# spuung-ap-v_0_0_1a.net
KiCad netlist of a schematic drawn in EAGLE
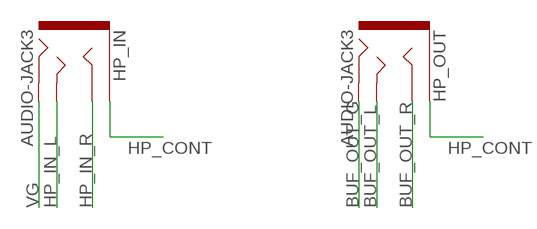
[diagram p0: schematic, sheet 1]
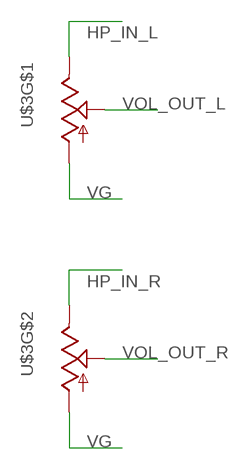
[diagram p1: schematic, sheet 2]
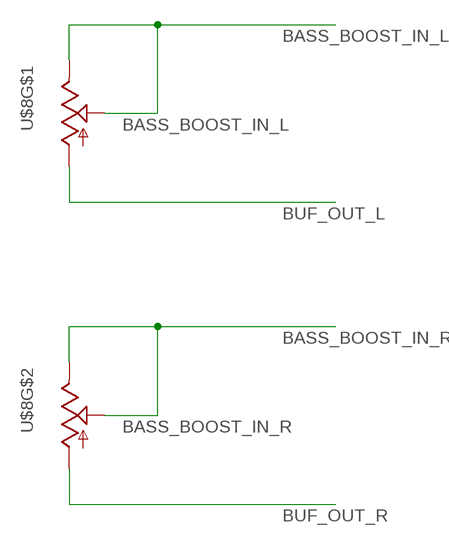
[diagram p2: schematic, sheet 3]
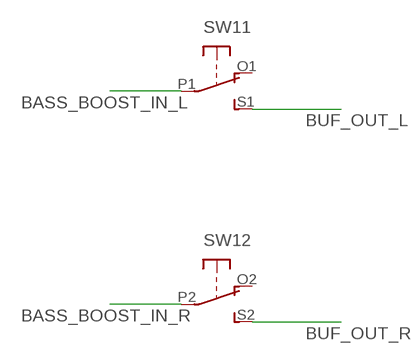
[diagram p3: schematic, sheet 4]
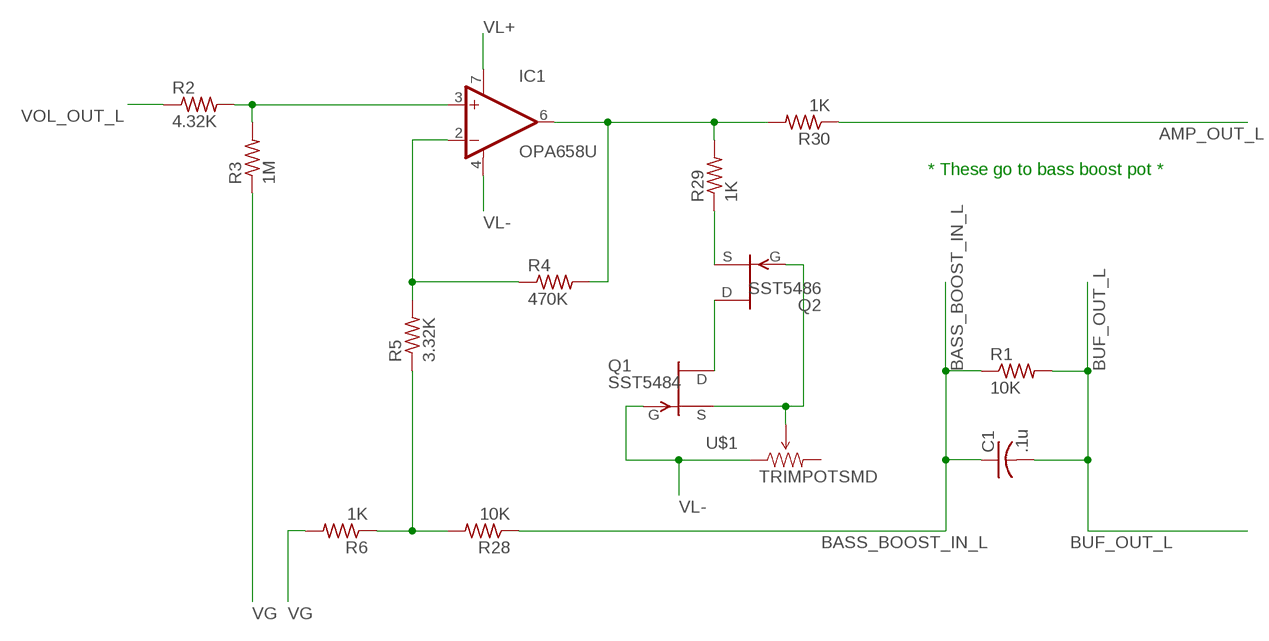
[diagram p4: schematic, sheet 5]
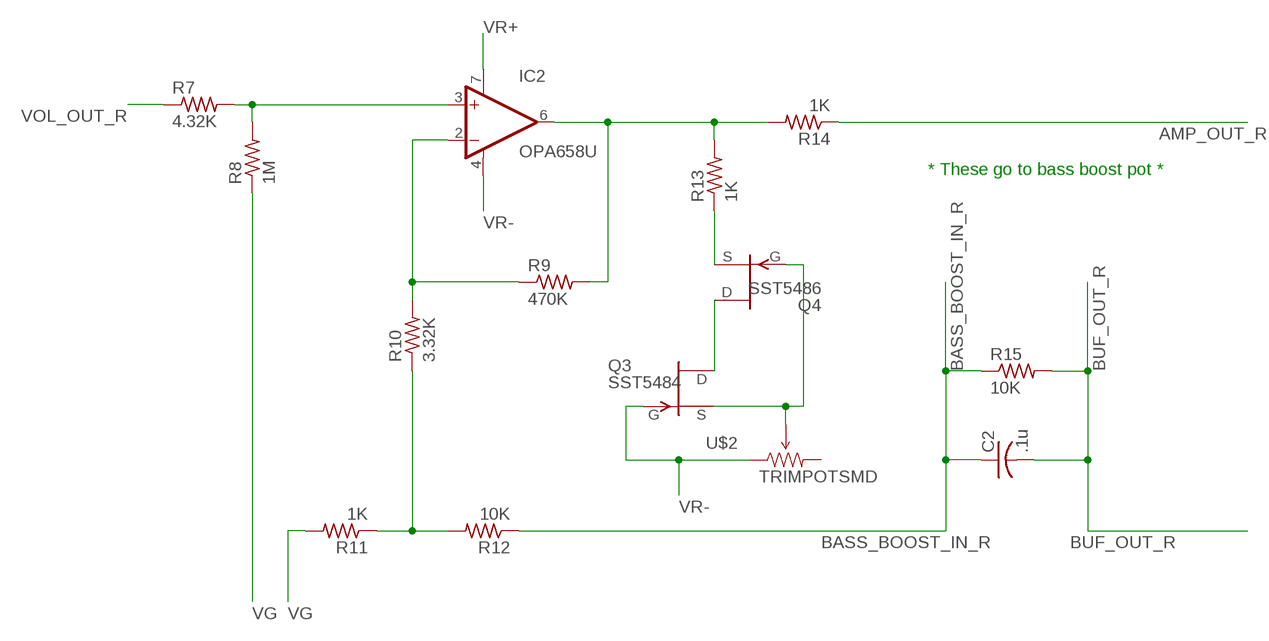
[diagram p5: schematic, sheet 6]
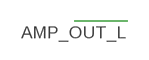
[diagram p6: schematic, sheet 7]
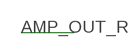
[diagram p7: schematic, sheet 8]

(export (version "E")
  (design (tool "Eeschema 10.0.6"))
  (components
    (comp (ref "HP_IN")
      (value "AUDIO-JACK3")
      (footprint "eagle-import:AUDIO-JACK-TRRS-SMD")
      (libsource (lib "eagle-import") (part "AUDIO-JACK3"))
    )
    (comp (ref "HP_OUT")
      (value "AUDIO-JACK3")
      (footprint "eagle-import:AUDIO-JACK-TRRS-SMD")
      (libsource (lib "eagle-import") (part "AUDIO-JACK3"))
    )
    (comp (ref "C1")
      (value ".1u")
      (footprint "eagle-import:C0805")
      (libsource (lib "eagle-import") (part "C-USC0805"))
    )
    (comp (ref "IC1")
      (value "OPA658U")
      (footprint "eagle-import:SO08")
      (fields (field (name "MPN") "AD8001ARZ"))
      (libsource (lib "eagle-import") (part "OPA658U"))
    )
    (comp (ref "Q1")
      (value "SST5484")
      (footprint "eagle-import:SOT23")
      (libsource (lib "eagle-import") (part "?548SST4"))
    )
    (comp (ref "Q2")
      (value "SST5486")
      (footprint "eagle-import:SOT23")
      (libsource (lib "eagle-import") (part "?548SST6"))
    )
    (comp (ref "R1")
      (value "10K")
      (footprint "eagle-import:R0805")
      (libsource (lib "eagle-import") (part "R-US_R0805"))
    )
    (comp (ref "R2")
      (value "4.32K")
      (footprint "eagle-import:R0805")
      (libsource (lib "eagle-import") (part "R-US_R0805"))
    )
    (comp (ref "R3")
      (value "1M")
      (footprint "eagle-import:R0805")
      (libsource (lib "eagle-import") (part "R-US_R0805"))
    )
    (comp (ref "R4")
      (value "470K")
      (footprint "eagle-import:R0805")
      (libsource (lib "eagle-import") (part "R-US_R0805"))
    )
    (comp (ref "R5")
      (value "3.32K")
      (footprint "eagle-import:R0805")
      (libsource (lib "eagle-import") (part "R-US_R0805"))
    )
    (comp (ref "R6")
      (value "1K")
      (footprint "eagle-import:R0805")
      (libsource (lib "eagle-import") (part "R-US_R0805"))
    )
    (comp (ref "R28")
      (value "10K")
      (footprint "eagle-import:R0805")
      (libsource (lib "eagle-import") (part "R-US_R0805"))
    )
    (comp (ref "R29")
      (value "1K")
      (footprint "eagle-import:R0805")
      (libsource (lib "eagle-import") (part "R-US_R0805"))
    )
    (comp (ref "R30")
      (value "1K")
      (footprint "eagle-import:R0805")
      (libsource (lib "eagle-import") (part "R-US_R0805"))
    )
    (comp (ref "U$1")
      (value "TRIMPOTSMD")
      (footprint "eagle-import:TRIMPOT-3MM")
      (libsource (lib "eagle-import") (part "TRIMPOTSMD"))
    )
    (comp (ref "U$8")
      (value "ALPS_BLUE")
      (footprint "eagle-import:ALPS_RK27")
      (libsource (lib "eagle-import") (part "ALPS_BLUE"))
    )
    (comp (ref "C2")
      (value ".1u")
      (footprint "eagle-import:C0805")
      (libsource (lib "eagle-import") (part "C-USC0805"))
    )
    (comp (ref "IC2")
      (value "OPA658U")
      (footprint "eagle-import:SO08")
      (fields (field (name "MPN") "AD8001ARZ"))
      (libsource (lib "eagle-import") (part "OPA658U"))
    )
    (comp (ref "Q3")
      (value "SST5484")
      (footprint "eagle-import:SOT23")
      (libsource (lib "eagle-import") (part "?548SST4"))
    )
    (comp (ref "Q4")
      (value "SST5486")
      (footprint "eagle-import:SOT23")
      (libsource (lib "eagle-import") (part "?548SST6"))
    )
    (comp (ref "R7")
      (value "4.32K")
      (footprint "eagle-import:R0805")
      (libsource (lib "eagle-import") (part "R-US_R0805"))
    )
    (comp (ref "R8")
      (value "1M")
      (footprint "eagle-import:R0805")
      (libsource (lib "eagle-import") (part "R-US_R0805"))
    )
    (comp (ref "R9")
      (value "470K")
      (footprint "eagle-import:R0805")
      (libsource (lib "eagle-import") (part "R-US_R0805"))
    )
    (comp (ref "R10")
      (value "3.32K")
      (footprint "eagle-import:R0805")
      (libsource (lib "eagle-import") (part "R-US_R0805"))
    )
    (comp (ref "R11")
      (value "1K")
      (footprint "eagle-import:R0805")
      (libsource (lib "eagle-import") (part "R-US_R0805"))
    )
    (comp (ref "R12")
      (value "10K")
      (footprint "eagle-import:R0805")
      (libsource (lib "eagle-import") (part "R-US_R0805"))
    )
    (comp (ref "R13")
      (value "1K")
      (footprint "eagle-import:R0805")
      (libsource (lib "eagle-import") (part "R-US_R0805"))
    )
    (comp (ref "R14")
      (value "1K")
      (footprint "eagle-import:R0805")
      (libsource (lib "eagle-import") (part "R-US_R0805"))
    )
    (comp (ref "R15")
      (value "10K")
      (footprint "eagle-import:R0805")
      (libsource (lib "eagle-import") (part "R-US_R0805"))
    )
    (comp (ref "U$2")
      (value "TRIMPOTSMD")
      (footprint "eagle-import:TRIMPOT-3MM")
      (libsource (lib "eagle-import") (part "TRIMPOTSMD"))
    )
    (comp (ref "U$3")
      (value "ALPS_BLUE")
      (footprint "eagle-import:ALPS_RK27")
      (libsource (lib "eagle-import") (part "ALPS_BLUE"))
    )
    (comp (ref "SW1")
      (value "DPDT-EG1390")
      (footprint "eagle-import:EG1390")
      (libsource (lib "eagle-import") (part "DPDT-EG1390"))
    )
  )
  (nets
    (net (code "1") (name "AMP_OUT_L") (class "Default")
      (node (ref "R30") (pin "1") (pinfunction "1_1") (pintype "passive"))
    )
    (net (code "2") (name "AMP_OUT_R") (class "Default")
      (node (ref "R14") (pin "1") (pinfunction "1_1") (pintype "passive"))
    )
    (net (code "3") (name "BASS_BOOST_IN_L") (class "Default")
      (node (ref "C1") (pin "1") (pinfunction "1_1") (pintype "passive"))
      (node (ref "R1") (pin "1") (pinfunction "1_1") (pintype "passive"))
      (node (ref "R28") (pin "1") (pinfunction "1_1") (pintype "passive"))
      (node (ref "SW1") (pin "P1") (pinfunction "P_P1") (pintype "passive"))
      (node (ref "U$8") (pin "I1") (pinfunction "3_I1") (pintype "passive"))
      (node (ref "U$8") (pin "O1") (pinfunction "2_O1") (pintype "passive"))
    )
    (net (code "4") (name "BASS_BOOST_IN_R") (class "Default")
      (node (ref "C2") (pin "1") (pinfunction "1_1") (pintype "passive"))
      (node (ref "R12") (pin "1") (pinfunction "1_1") (pintype "passive"))
      (node (ref "R15") (pin "1") (pinfunction "1_1") (pintype "passive"))
      (node (ref "SW1") (pin "P2") (pinfunction "P_P2") (pintype "passive"))
      (node (ref "U$8") (pin "I2") (pinfunction "3_I2") (pintype "passive"))
      (node (ref "U$8") (pin "O2") (pinfunction "2_O2") (pintype "passive"))
    )
    (net (code "5") (name "BUF_OUT_G") (class "Default")
      (node (ref "HP_OUT") (pin "RING2") (pinfunction "RING2_RING2") (pintype "bidirectional"))
    )
    (net (code "6") (name "BUF_OUT_L") (class "Default")
      (node (ref "C1") (pin "2") (pinfunction "2_2") (pintype "passive"))
      (node (ref "HP_OUT") (pin "TIP") (pinfunction "TIP_TIP") (pintype "bidirectional"))
      (node (ref "R1") (pin "2") (pinfunction "2_2") (pintype "passive"))
      (node (ref "SW1") (pin "S1") (pinfunction "S_S1") (pintype "passive"))
      (node (ref "U$8") (pin "G1") (pinfunction "1_G1") (pintype "passive"))
    )
    (net (code "7") (name "BUF_OUT_R") (class "Default")
      (node (ref "C2") (pin "2") (pinfunction "2_2") (pintype "passive"))
      (node (ref "HP_OUT") (pin "RING1") (pinfunction "RING1_RING1") (pintype "bidirectional"))
      (node (ref "R15") (pin "2") (pinfunction "2_2") (pintype "passive"))
      (node (ref "SW1") (pin "S2") (pinfunction "S_S2") (pintype "passive"))
      (node (ref "U$8") (pin "G2") (pinfunction "1_G2") (pintype "passive"))
    )
    (net (code "8") (name "HP_CONT") (class "Default")
      (node (ref "HP_IN") (pin "EARTH") (pinfunction "EARTH_EARTH") (pintype "bidirectional"))
      (node (ref "HP_OUT") (pin "EARTH") (pinfunction "EARTH_EARTH") (pintype "bidirectional"))
    )
    (net (code "9") (name "HP_IN_L") (class "Default")
      (node (ref "HP_IN") (pin "TIP") (pinfunction "TIP_TIP") (pintype "bidirectional"))
      (node (ref "U$3") (pin "I1") (pinfunction "3_I1") (pintype "passive"))
    )
    (net (code "10") (name "HP_IN_R") (class "Default")
      (node (ref "HP_IN") (pin "RING1") (pinfunction "RING1_RING1") (pintype "bidirectional"))
      (node (ref "U$3") (pin "I2") (pinfunction "3_I2") (pintype "passive"))
    )
    (net (code "11") (name "Net-(IC1-+IN)") (class "Default")
      (node (ref "IC1") (pin "3") (pinfunction "+IN_3") (pintype "input"))
      (node (ref "R2") (pin "2") (pinfunction "2_2") (pintype "passive"))
      (node (ref "R3") (pin "2") (pinfunction "2_2") (pintype "passive"))
    )
    (net (code "12") (name "Net-(IC1--IN)") (class "Default")
      (node (ref "IC1") (pin "2") (pinfunction "-IN_2") (pintype "input"))
      (node (ref "R4") (pin "1") (pinfunction "1_1") (pintype "passive"))
      (node (ref "R5") (pin "2") (pinfunction "2_2") (pintype "passive"))
    )
    (net (code "13") (name "Net-(IC1-OUT)") (class "Default")
      (node (ref "IC1") (pin "6") (pinfunction "OUT_6") (pintype "output"))
      (node (ref "R29") (pin "2") (pinfunction "2_2") (pintype "passive"))
      (node (ref "R30") (pin "2") (pinfunction "2_2") (pintype "passive"))
      (node (ref "R4") (pin "2") (pinfunction "2_2") (pintype "passive"))
    )
    (net (code "14") (name "Net-(IC2-+IN)") (class "Default")
      (node (ref "IC2") (pin "3") (pinfunction "+IN_3") (pintype "input"))
      (node (ref "R7") (pin "2") (pinfunction "2_2") (pintype "passive"))
      (node (ref "R8") (pin "2") (pinfunction "2_2") (pintype "passive"))
    )
    (net (code "15") (name "Net-(IC2--IN)") (class "Default")
      (node (ref "IC2") (pin "2") (pinfunction "-IN_2") (pintype "input"))
      (node (ref "R10") (pin "2") (pinfunction "2_2") (pintype "passive"))
      (node (ref "R9") (pin "1") (pinfunction "1_1") (pintype "passive"))
    )
    (net (code "16") (name "Net-(IC2-OUT)") (class "Default")
      (node (ref "IC2") (pin "6") (pinfunction "OUT_6") (pintype "output"))
      (node (ref "R13") (pin "2") (pinfunction "2_2") (pintype "passive"))
      (node (ref "R14") (pin "2") (pinfunction "2_2") (pintype "passive"))
      (node (ref "R9") (pin "2") (pinfunction "2_2") (pintype "passive"))
    )
    (net (code "17") (name "Net-(Q1-D)") (class "Default")
      (node (ref "Q1") (pin "1") (pinfunction "D_1") (pintype "passive"))
      (node (ref "Q2") (pin "1") (pinfunction "D_1") (pintype "passive"))
    )
    (net (code "18") (name "Net-(Q1-S)") (class "Default")
      (node (ref "Q1") (pin "2") (pinfunction "S_2") (pintype "passive"))
      (node (ref "Q2") (pin "3") (pinfunction "G_3") (pintype "passive"))
      (node (ref "U$1") (pin "2") (pinfunction "WIPER_2") (pintype "passive"))
    )
    (net (code "19") (name "Net-(Q2-S)") (class "Default")
      (node (ref "Q2") (pin "2") (pinfunction "S_2") (pintype "passive"))
      (node (ref "R29") (pin "1") (pinfunction "1_1") (pintype "passive"))
    )
    (net (code "20") (name "Net-(Q3-D)") (class "Default")
      (node (ref "Q3") (pin "1") (pinfunction "D_1") (pintype "passive"))
      (node (ref "Q4") (pin "1") (pinfunction "D_1") (pintype "passive"))
    )
    (net (code "21") (name "Net-(Q3-S)") (class "Default")
      (node (ref "Q3") (pin "2") (pinfunction "S_2") (pintype "passive"))
      (node (ref "Q4") (pin "3") (pinfunction "G_3") (pintype "passive"))
      (node (ref "U$2") (pin "2") (pinfunction "WIPER_2") (pintype "passive"))
    )
    (net (code "22") (name "Net-(Q4-S)") (class "Default")
      (node (ref "Q4") (pin "2") (pinfunction "S_2") (pintype "passive"))
      (node (ref "R13") (pin "1") (pinfunction "1_1") (pintype "passive"))
    )
    (net (code "23") (name "Net-(R10-Pad1)") (class "Default")
      (node (ref "R10") (pin "1") (pinfunction "1_1") (pintype "passive"))
      (node (ref "R11") (pin "1") (pinfunction "1_1") (pintype "passive"))
      (node (ref "R12") (pin "2") (pinfunction "2_2") (pintype "passive"))
    )
    (net (code "24") (name "Net-(R28-Pad2)") (class "Default")
      (node (ref "R28") (pin "2") (pinfunction "2_2") (pintype "passive"))
      (node (ref "R5") (pin "1") (pinfunction "1_1") (pintype "passive"))
      (node (ref "R6") (pin "1") (pinfunction "1_1") (pintype "passive"))
    )
    (net (code "25") (name "VG") (class "Default")
      (node (ref "HP_IN") (pin "RING2") (pinfunction "RING2_RING2") (pintype "bidirectional"))
      (node (ref "R11") (pin "2") (pinfunction "2_2") (pintype "passive"))
      (node (ref "R3") (pin "1") (pinfunction "1_1") (pintype "passive"))
      (node (ref "R6") (pin "2") (pinfunction "2_2") (pintype "passive"))
      (node (ref "R8") (pin "1") (pinfunction "1_1") (pintype "passive"))
      (node (ref "U$3") (pin "G1") (pinfunction "1_G1") (pintype "passive"))
      (node (ref "U$3") (pin "G2") (pinfunction "1_G2") (pintype "passive"))
    )
    (net (code "26") (name "VL+") (class "Default")
      (node (ref "IC1") (pin "7") (pinfunction "V+_7") (pintype "power_in"))
    )
    (net (code "27") (name "VL-") (class "Default")
      (node (ref "IC1") (pin "4") (pinfunction "V-_4") (pintype "power_in"))
      (node (ref "Q1") (pin "3") (pinfunction "G_3") (pintype "passive"))
      (node (ref "U$1") (pin "1") (pinfunction "CCW_1") (pintype "passive"))
    )
    (net (code "28") (name "VOL_OUT_L") (class "Default")
      (node (ref "R2") (pin "1") (pinfunction "1_1") (pintype "passive"))
      (node (ref "U$3") (pin "O1") (pinfunction "2_O1") (pintype "passive"))
    )
    (net (code "29") (name "VOL_OUT_R") (class "Default")
      (node (ref "R7") (pin "1") (pinfunction "1_1") (pintype "passive"))
      (node (ref "U$3") (pin "O2") (pinfunction "2_O2") (pintype "passive"))
    )
    (net (code "30") (name "VR+") (class "Default")
      (node (ref "IC2") (pin "7") (pinfunction "V+_7") (pintype "power_in"))
    )
    (net (code "31") (name "VR-") (class "Default")
      (node (ref "IC2") (pin "4") (pinfunction "V-_4") (pintype "power_in"))
      (node (ref "Q3") (pin "3") (pinfunction "G_3") (pintype "passive"))
      (node (ref "U$2") (pin "1") (pinfunction "CCW_1") (pintype "passive"))
    )
    (net (code "32") (name "unconnected-(SW1A-O-PadO1)") (class "Default")
      (node (ref "SW1") (pin "O1") (pinfunction "O_O1") (pintype "passive"))
    )
    (net (code "33") (name "unconnected-(SW1B-O-PadO2)") (class "Default")
      (node (ref "SW1") (pin "O2") (pinfunction "O_O2") (pintype "passive"))
    )
    (net (code "34") (name "unconnected-(U$1-CW-Pad3)") (class "Default")
      (node (ref "U$1") (pin "3") (pinfunction "CW_3") (pintype "passive"))
    )
    (net (code "35") (name "unconnected-(U$2-CW-Pad3)") (class "Default")
      (node (ref "U$2") (pin "3") (pinfunction "CW_3") (pintype "passive"))
    )
  )
)
